# TCAN1146_PINOUT.net
KiCad netlist of a schematic drawn in Altium Designer
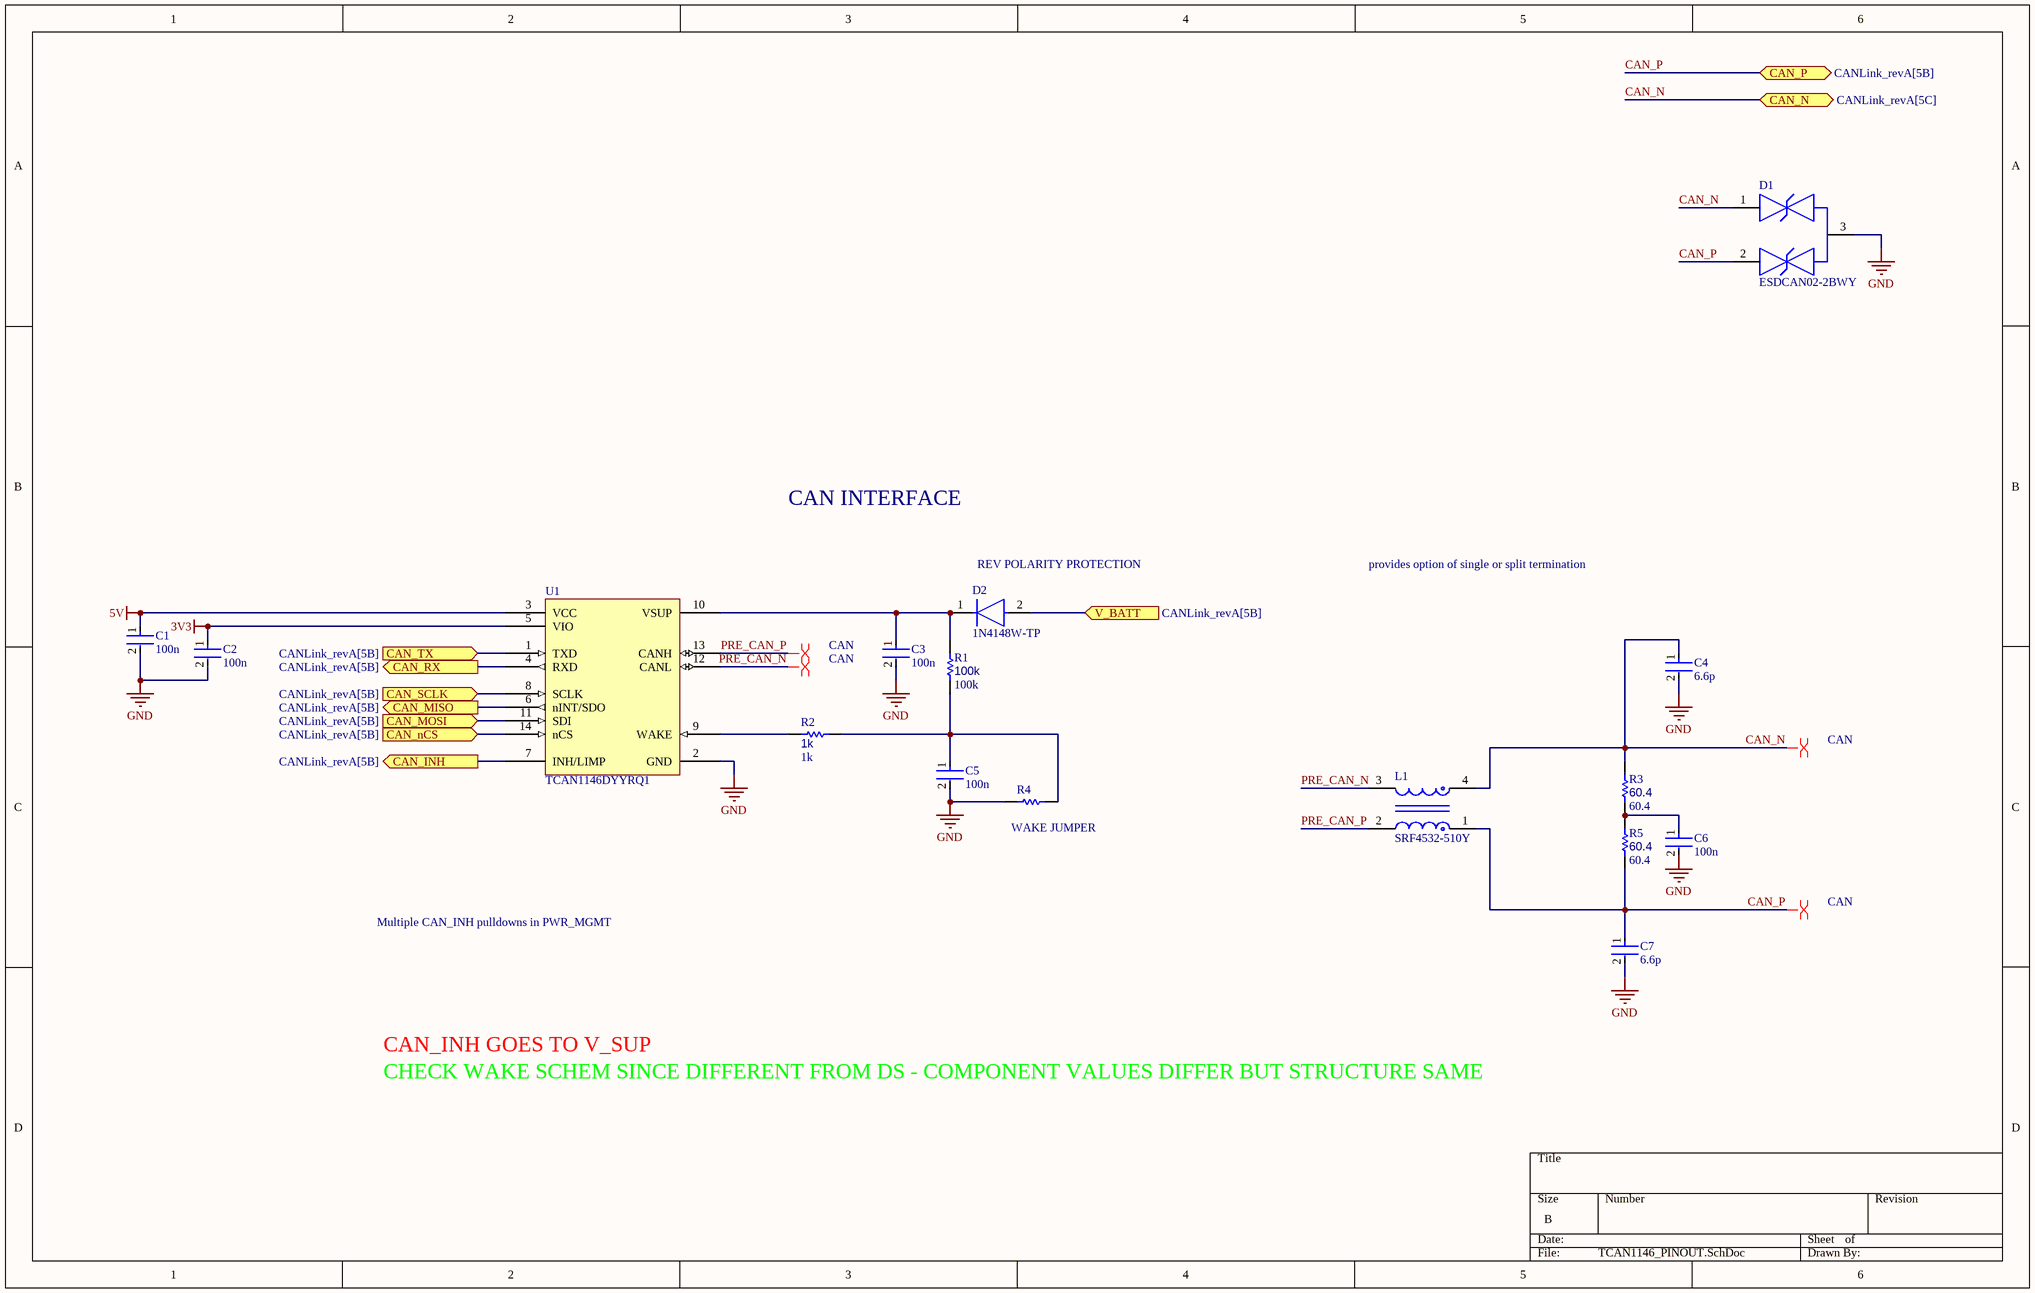
[diagram p0: TCAN1146_PINOUT.SchDoc]

(export (version "E")
  (design (tool "Eeschema 10.0.6"))
  (components
    (comp (ref "C1")
      (value "100n")
      (footprint "FP-0402-L_1_0_0_05-W_0_5-IPC_A")
      (description "LARGE PADS, 0402 CAP, CHANGE COMMENT TO MATCH REAL P/N")
      (libsource (lib "Space Concordia") (part "b4654b650e69147ec39a6b967a45e02"))
    )
    (comp (ref "C2")
      (value "100n")
      (footprint "FP-0402-L_1_0_0_05-W_0_5-IPC_A")
      (description "LARGE PADS, 0402 CAP, CHANGE COMMENT TO MATCH REAL P/N")
      (libsource (lib "Space Concordia") (part "b4654b650e69147ec39a6b967a45e02"))
    )
    (comp (ref "C3")
      (value "100n")
      (footprint "FP-0402-L_1_0_0_05-W_0_5-IPC_A")
      (description "LARGE PADS, 0402 CAP, CHANGE COMMENT TO MATCH REAL P/N")
      (libsource (lib "Space Concordia") (part "b4654b650e69147ec39a6b967a45e02"))
    )
    (comp (ref "C4")
      (value "6.6p")
      (footprint "FP-0402-L_1_0_0_05-W_0_5-IPC_A")
      (description "LARGE PADS, 0402 CAP, CHANGE COMMENT TO MATCH REAL P/N")
      (libsource (lib "Space Concordia") (part "b4654b650e69147ec39a6b967a45e02"))
    )
    (comp (ref "C5")
      (value "100n")
      (footprint "FP-0402-L_1_0_0_05-W_0_5-IPC_A")
      (description "LARGE PADS, 0402 CAP, CHANGE COMMENT TO MATCH REAL P/N")
      (libsource (lib "Space Concordia") (part "b4654b650e69147ec39a6b967a45e02"))
    )
    (comp (ref "C6")
      (value "100n")
      (footprint "FP-0402-L_1_0_0_05-W_0_5-IPC_A")
      (description "LARGE PADS, 0402 CAP, CHANGE COMMENT TO MATCH REAL P/N")
      (libsource (lib "Space Concordia") (part "b4654b650e69147ec39a6b967a45e02"))
    )
    (comp (ref "C7")
      (value "6.6p")
      (footprint "FP-0402-L_1_0_0_05-W_0_5-IPC_A")
      (description "LARGE PADS, 0402 CAP, CHANGE COMMENT TO MATCH REAL P/N")
      (libsource (lib "Space Concordia") (part "b4654b650e69147ec39a6b967a45e02"))
    )
    (comp (ref "D1")
      (value "ESDCAN02-2BWY")
      (footprint "FP-SOT323-3L-MFG")
      (description "TVS DIODE 26.5V 44V SOT323-3")
      (fields
        (field (name "MANUFACTURER") "STMicroelectronics")
        (field (name "OCTOPART") "https://octopart.com/esdcan02-2bwy-stmicroelectronics-58631133")
      )
      (libsource (lib "Altium Content Vault") (part "0b9019fb5e52ed66df21ec1535be59d"))
    )
    (comp (ref "D2")
      (value "1N4148W-TP")
      (footprint "FP-SOD-123-IPC_A")
      (description "DIODE GEN PURP 100V 150MA SOD123")
      (libsource (lib "Altium Content Vault") (part "d7152d700b627762746794eb795d46e"))
    )
    (comp (ref "L1")
      (value "SRF4532-510Y")
      (footprint "FP-SRF4532-MFG")
      (description "CMC 51UH 200MA 2LN 2KOHM SMD")
      (fields (field (name "TOLERANCE") "50%"))
      (libsource (lib "Altium Content Vault") (part "aca3f6a10b859f211cca95010157f3b"))
    )
    (comp (ref "R1")
      (value "100k")
      (footprint "R0603B")
      (description "Resistor")
      (fields (field (name "ALTIUM_VALUE") "100k"))
      (libsource (lib "Space Concordia") (part "Resistor"))
    )
    (comp (ref "R2")
      (value "1k")
      (footprint "R0603B")
      (description "Resistor")
      (fields (field (name "ALTIUM_VALUE") "1k"))
      (libsource (lib "Space Concordia") (part "Resistor"))
    )
    (comp (ref "R3")
      (value "60.4")
      (footprint "R0603B")
      (description "Resistor")
      (fields (field (name "ALTIUM_VALUE") "60.4"))
      (libsource (lib "Space Concordia") (part "Resistor"))
    )
    (comp (ref "R4")
      (value "0402 JUMPER")
      (footprint "RESC1005X40X25ML05T05")
      (description "READ THE NAME")
      (libsource (lib "Space Concordia") (part "CMP-009-00206-2"))
    )
    (comp (ref "R5")
      (value "60.4")
      (footprint "R0603B")
      (description "Resistor")
      (fields (field (name "ALTIUM_VALUE") "60.4"))
      (libsource (lib "Space Concordia") (part "Resistor"))
    )
    (comp (ref "U1")
      (value "TCAN1146DYYRQ1")
      (footprint "TCAN1146DYYRQ1-Footprint-1")
      (libsource (lib "Space Concordia") (part "CMP-015-00012-2"))
    )
  )
  (nets
    (net (code "1") (name "/CAN_INH") (class "Default")
      (node (ref "U1") (pin "7") (pinfunction "INH/LIMP_7") (pintype "passive"))
    )
    (net (code "2") (name "/CAN_MISO") (class "Default")
      (node (ref "U1") (pin "6") (pinfunction "nINT/SDO_6") (pintype "output"))
    )
    (net (code "3") (name "/CAN_MOSI") (class "Default")
      (node (ref "U1") (pin "11") (pinfunction "SDI_11") (pintype "input"))
    )
    (net (code "4") (name "/CAN_N") (class "Default")
      (node (ref "C4") (pin "1") (pinfunction "1_1") (pintype "passive"))
      (node (ref "D1") (pin "1") (pinfunction "1_1") (pintype "passive"))
      (node (ref "L1") (pin "4") (pinfunction "4_4") (pintype "passive"))
      (node (ref "R3") (pin "1") (pinfunction "1_1") (pintype "passive"))
    )
    (net (code "5") (name "/CAN_P") (class "Default")
      (node (ref "C7") (pin "1") (pinfunction "1_1") (pintype "passive"))
      (node (ref "D1") (pin "2") (pinfunction "2_2") (pintype "passive"))
      (node (ref "L1") (pin "1") (pinfunction "1_1") (pintype "passive"))
      (node (ref "R5") (pin "2") (pinfunction "2_2") (pintype "passive"))
    )
    (net (code "6") (name "/CAN_RX") (class "Default")
      (node (ref "U1") (pin "4") (pinfunction "RXD_4") (pintype "output"))
    )
    (net (code "7") (name "/CAN_SCLK") (class "Default")
      (node (ref "U1") (pin "8") (pinfunction "SCLK_8") (pintype "input"))
    )
    (net (code "8") (name "/CAN_TX") (class "Default")
      (node (ref "U1") (pin "1") (pinfunction "TXD_1") (pintype "input"))
    )
    (net (code "9") (name "/CAN_nCS") (class "Default")
      (node (ref "U1") (pin "14") (pinfunction "nCS_14") (pintype "input"))
    )
    (net (code "10") (name "/PRE_CAN_N") (class "Default")
      (node (ref "L1") (pin "3") (pinfunction "3_3") (pintype "passive"))
      (node (ref "U1") (pin "12") (pinfunction "CANL_12") (pintype "bidirectional"))
    )
    (net (code "11") (name "/PRE_CAN_P") (class "Default")
      (node (ref "L1") (pin "2") (pinfunction "2_2") (pintype "passive"))
      (node (ref "U1") (pin "13") (pinfunction "CANH_13") (pintype "bidirectional"))
    )
    (net (code "12") (name "/V_BATT") (class "Default")
      (node (ref "D2") (pin "2") (pinfunction "A_2") (pintype "passive"))
    )
    (net (code "13") (name "3V3") (class "Default")
      (node (ref "C2") (pin "1") (pinfunction "1_1") (pintype "passive"))
      (node (ref "U1") (pin "5") (pinfunction "VIO_5") (pintype "power_in"))
    )
    (net (code "14") (name "5V") (class "Default")
      (node (ref "C1") (pin "1") (pinfunction "1_1") (pintype "passive"))
      (node (ref "U1") (pin "3") (pinfunction "VCC_3") (pintype "power_in"))
    )
    (net (code "15") (name "GND") (class "Default")
      (node (ref "C1") (pin "2") (pinfunction "2_2") (pintype "passive"))
      (node (ref "C2") (pin "2") (pinfunction "2_2") (pintype "passive"))
      (node (ref "C3") (pin "2") (pinfunction "2_2") (pintype "passive"))
      (node (ref "C4") (pin "2") (pinfunction "2_2") (pintype "passive"))
      (node (ref "C5") (pin "2") (pinfunction "2_2") (pintype "passive"))
      (node (ref "C6") (pin "2") (pinfunction "2_2") (pintype "passive"))
      (node (ref "C7") (pin "2") (pinfunction "2_2") (pintype "passive"))
      (node (ref "D1") (pin "3") (pinfunction "3_3") (pintype "passive"))
      (node (ref "R4") (pin "1") (pinfunction "1_1") (pintype "passive"))
      (node (ref "U1") (pin "2") (pinfunction "GND_2") (pintype "power_in"))
    )
    (net (code "16") (name "Net-(C5-Pad1)") (class "Default")
      (node (ref "C5") (pin "1") (pinfunction "1_1") (pintype "passive"))
      (node (ref "R1") (pin "2") (pinfunction "2_2") (pintype "passive"))
      (node (ref "R2") (pin "2") (pinfunction "2_2") (pintype "passive"))
      (node (ref "R4") (pin "2") (pinfunction "2_2") (pintype "passive"))
    )
    (net (code "17") (name "Net-(C6-Pad1)") (class "Default")
      (node (ref "C6") (pin "1") (pinfunction "1_1") (pintype "passive"))
      (node (ref "R3") (pin "2") (pinfunction "2_2") (pintype "passive"))
      (node (ref "R5") (pin "1") (pinfunction "1_1") (pintype "passive"))
    )
    (net (code "18") (name "Net-(D2-C)") (class "Default")
      (node (ref "C3") (pin "1") (pinfunction "1_1") (pintype "passive"))
      (node (ref "D2") (pin "1") (pinfunction "C_1") (pintype "passive"))
      (node (ref "R1") (pin "1") (pinfunction "1_1") (pintype "passive"))
      (node (ref "U1") (pin "10") (pinfunction "VSUP_10") (pintype "power_in"))
    )
    (net (code "19") (name "Net-(U1-WAKE)") (class "Default")
      (node (ref "R2") (pin "1") (pinfunction "1_1") (pintype "passive"))
      (node (ref "U1") (pin "9") (pinfunction "WAKE_9") (pintype "input"))
    )
  )
)
